# LCD_LED.net
KiCad netlist of a schematic drawn in Altium Designer
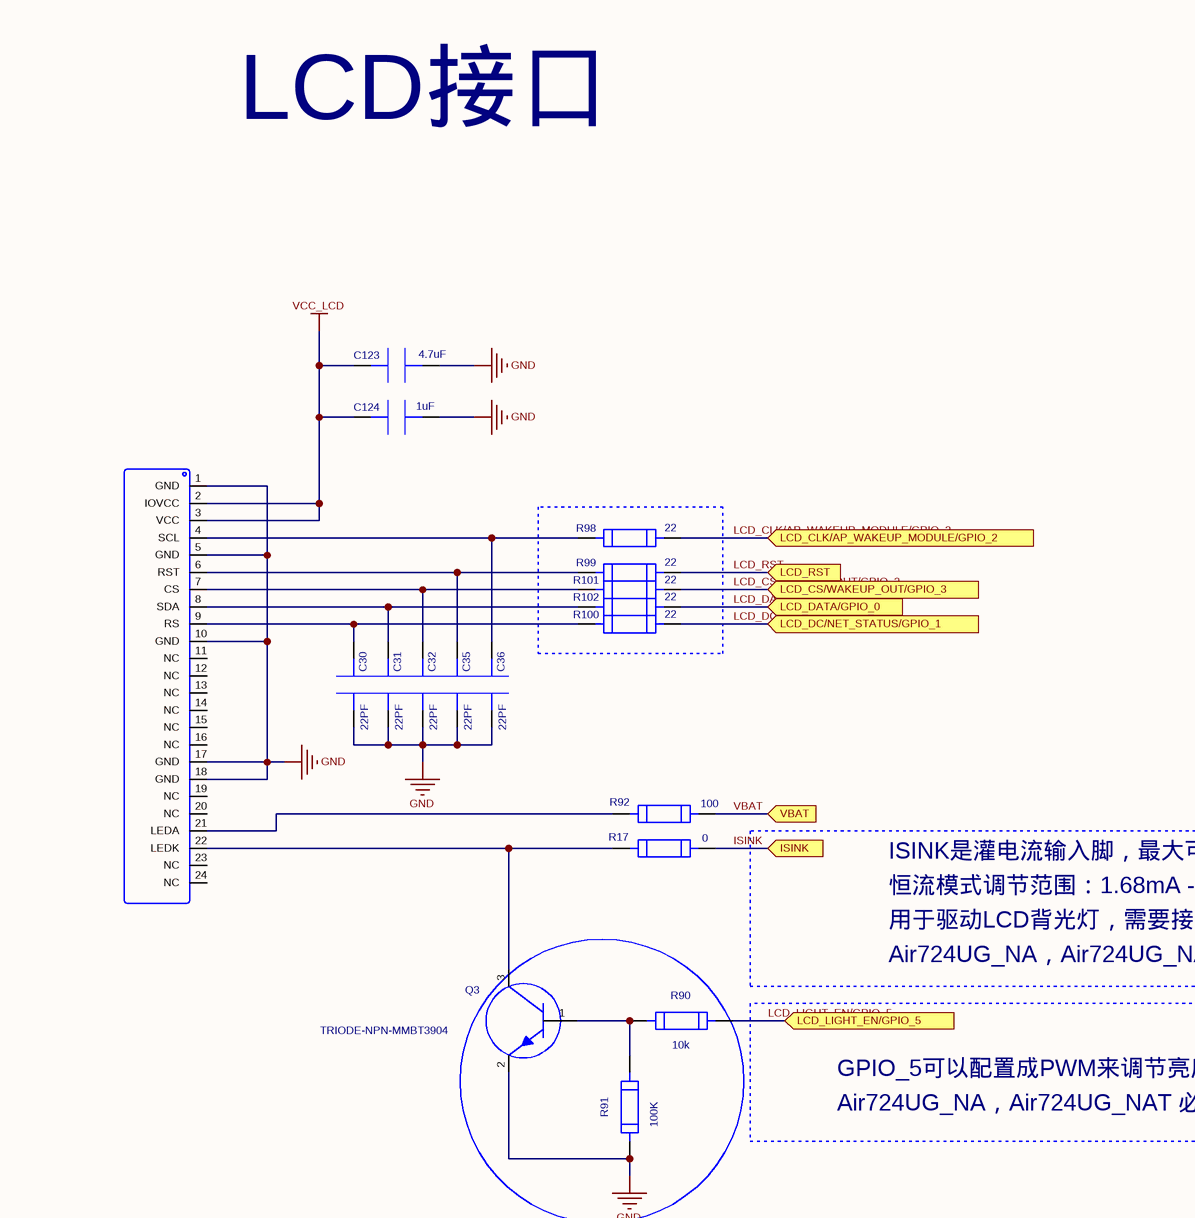
[diagram p0: LCD_LED.SchDoc, top left]
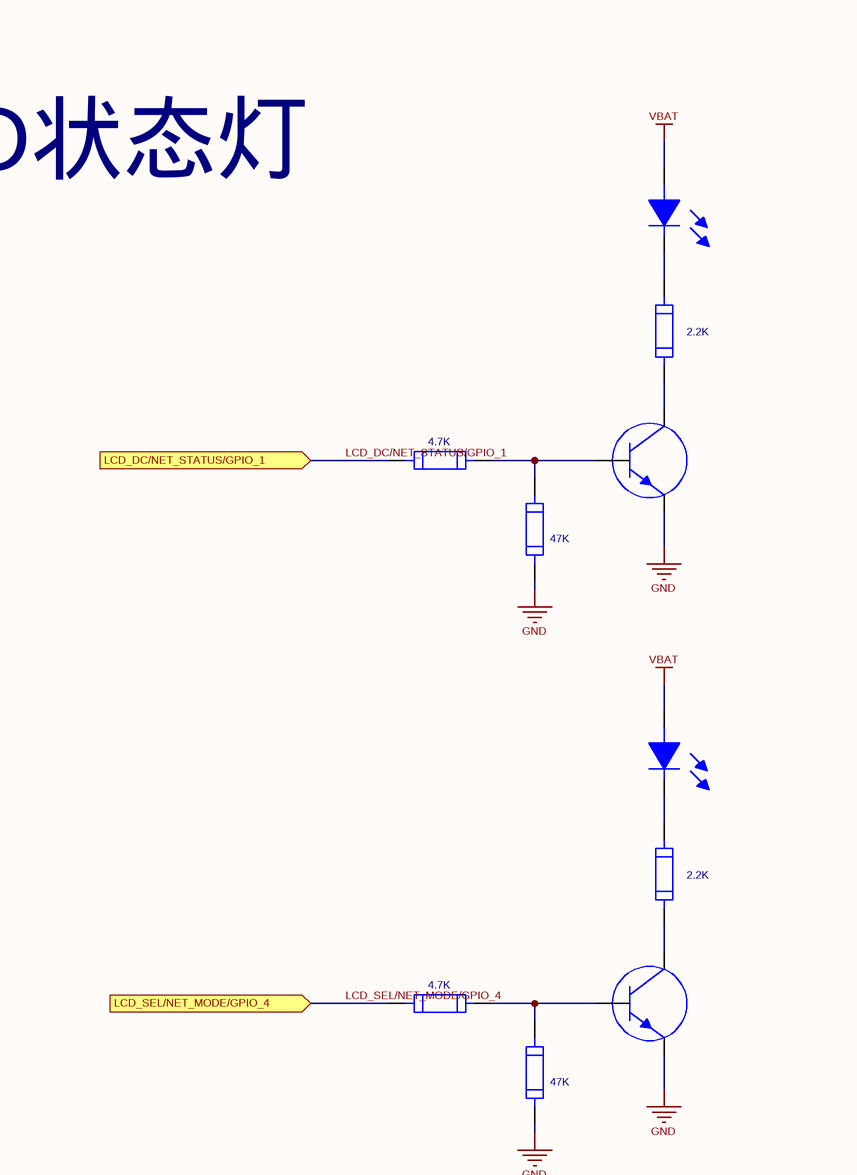
[diagram p1: LCD_LED.SchDoc, top right]
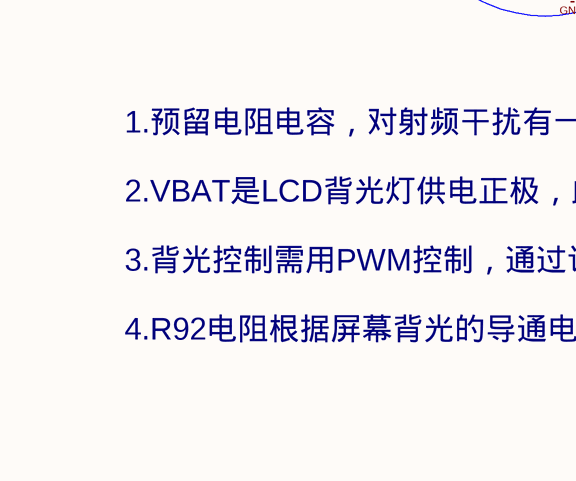
[diagram p2: LCD_LED.SchDoc, bottom left]
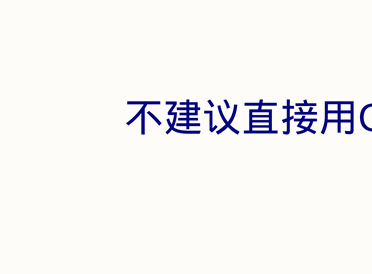
[diagram p3: LCD_LED.SchDoc, bottom middle]
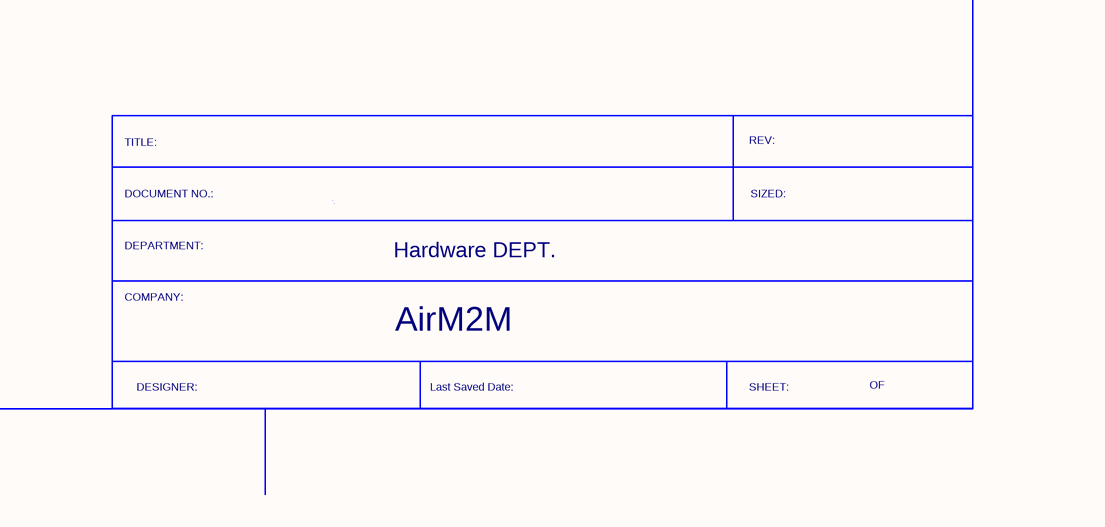
[diagram p4: LCD_LED.SchDoc, bottom right]

(export (version "E")
  (design (tool "Eeschema 10.0.6"))
  (components
    (comp (ref "C30")
      (value "22PF")
      (footprint "SC0402")
      (description "CAP CER C0G;22PF;+/-5%;50V;0402;0.5mm;ROHS")
      (fields (field (name "TOLERANCE") "+/-5%;") (field (name "Comment") "CAP-22PF-0402-C0G"))
      (libsource (lib "*") (part "CAP-22PF-0402-C0G"))
    )
    (comp (ref "C31")
      (value "22PF")
      (footprint "SC0402")
      (description "CAP CER C0G;22PF;+/-5%;50V;0402;0.5mm;ROHS")
      (fields (field (name "TOLERANCE") "+/-5%;") (field (name "Comment") "CAP-22PF-0402-C0G"))
      (libsource (lib "*") (part "CAP-22PF-0402-C0G"))
    )
    (comp (ref "C32")
      (value "22PF")
      (footprint "SC0402")
      (description "CAP CER C0G;22PF;+/-5%;50V;0402;0.5mm;ROHS")
      (fields (field (name "TOLERANCE") "+/-5%;") (field (name "Comment") "CAP-22PF-0402-C0G"))
      (libsource (lib "*") (part "CAP-22PF-0402-C0G"))
    )
    (comp (ref "C35")
      (value "22PF")
      (footprint "SC0402")
      (description "CAP CER C0G;22PF;+/-5%;50V;0402;0.5mm;ROHS")
      (fields (field (name "TOLERANCE") "+/-5%;") (field (name "Comment") "CAP-22PF-0402-C0G"))
      (libsource (lib "*") (part "CAP-22PF-0402-C0G"))
    )
    (comp (ref "C36")
      (value "22PF")
      (footprint "SC0402")
      (description "CAP CER C0G;22PF;+/-5%;50V;0402;0.5mm;ROHS")
      (fields (field (name "TOLERANCE") "+/-5%;") (field (name "Comment") "CAP-22PF-0402-C0G"))
      (libsource (lib "*") (part "CAP-22PF-0402-C0G"))
    )
    (comp (ref "C123")
      (value "4.7uF")
      (footprint "SC0603")
      (description "CAP CER X5R;4.7uF;+/-10%;6.3V;0603;0.8mm;ROHS")
      (fields (field (name "TOLERANCE") "+/-10%") (field (name "Comment") "CAP-4.7UF-0603-X5R"))
      (libsource (lib "*") (part "CAP-4.7UF-0603-X5R"))
    )
    (comp (ref "C124")
      (value "1uF")
      (footprint "SC0402")
      (description "CAP CER X5R;1uF;+/-10%;6.3V;0402;0.5mm;ROHS")
      (fields (field (name "TOLERANCE") "+/-10%") (field (name "Comment") "CAP-1UF-0402-X5R"))
      (libsource (lib "*") (part "CAP-1UF-0402-X5R"))
    )
    (comp (ref "D1")
      (value "DIODE-LED-RED-2.54")
      (footprint "DIP2X1-2.54")
      (description "LED red")
      (libsource (lib "*") (part "DIODE-LED-RED-2.54"))
    )
    (comp (ref "D3")
      (value "DIODE-LED-RED-2.54")
      (footprint "DIP2X1-2.54")
      (description "LED red")
      (libsource (lib "*") (part "DIODE-LED-RED-2.54"))
    )
    (comp (ref "P6")
      (value "FPC_0.5MM_24P_PULL_TYPE_H2.0MM_UNDER_THE")
      (footprint "FPC-SMD_AFC07-S24FCC-00")
      (fields
        (field (name "BOM_SUPPLIER_PART") "C11057")
        (field (name "BOM_MANUFACTURER_PART") "FPC 0.5MM 24P Pull type H2.0mm Under the next")
      )
      (libsource (lib "*") (part "FPC_0.5MM_24P_PULL_TYPE_H2.0MM_UNDER_THE"))
    )
    (comp (ref "Q3")
      (value "TRIODE-NPN-MMBT3904")
      (footprint "SOT-23(MMBT3904)")
      (description "Transistor;NPN;40V;200mA;SOT23;1.1mm;ROHS")
      (libsource (lib "") (part "TRIODE-NPN-MMBT3904_1"))
    )
    (comp (ref "Q5")
      (value "TRIODE-NPN-MMBT3904")
      (footprint "SOT-23(MMBT3904)")
      (description "Transistor;NPN;40V;200mA;SOT23;1.1mm;ROHS")
      (libsource (lib "*") (part "TRIODE-NPN-MMBT3904"))
    )
    (comp (ref "Q6")
      (value "TRIODE-NPN-MMBT3904")
      (footprint "SOT-23(MMBT3904)")
      (description "Transistor;NPN;40V;200mA;SOT23;1.1mm;ROHS")
      (libsource (lib "*") (part "TRIODE-NPN-MMBT3904"))
    )
    (comp (ref "R17")
      (value "0")
      (footprint "SR0402")
      (description "RES FILM;0;1A;0402;0.4mm;ROHS")
      (fields (field (name "Comment") "RES-0-0402"))
      (libsource (lib "*") (part "RES-0-0402"))
    )
    (comp (ref "R24")
      (value "4.7K")
      (footprint "SR0402")
      (description "RES FILM;4.7K;+/-5%;1/16W;0402;0.4mm;ROHS")
      (fields (field (name "TOLERANCE") "+/-5%") (field (name "Comment") "RES-4.7K-0402"))
      (libsource (lib "*") (part "RES-4.7K-0402"))
    )
    (comp (ref "R30")
      (value "47K")
      (footprint "SR0402")
      (description "RES FILM;4.7K;+/-5%;1/16W;0402;0.4mm;ROHS")
      (fields (field (name "TOLERANCE") "+/-5%") (field (name "Comment") "RES-4.7K-0402"))
      (libsource (lib "*") (part "RES-4.7K-0402"))
    )
    (comp (ref "R31")
      (value "2.2K")
      (footprint "SR0402")
      (description "RES FILM;4.7K;+/-5%;1/16W;0402;0.4mm;ROHS")
      (fields (field (name "TOLERANCE") "+/-5%") (field (name "Comment") "RES-4.7K-0402"))
      (libsource (lib "*") (part "RES-4.7K-0402"))
    )
    (comp (ref "R32")
      (value "4.7K")
      (footprint "SR0402")
      (description "RES FILM;4.7K;+/-5%;1/16W;0402;0.4mm;ROHS")
      (fields (field (name "TOLERANCE") "+/-5%") (field (name "Comment") "RES-4.7K-0402"))
      (libsource (lib "*") (part "RES-4.7K-0402"))
    )
    (comp (ref "R33")
      (value "47K")
      (footprint "SR0402")
      (description "RES FILM;4.7K;+/-5%;1/16W;0402;0.4mm;ROHS")
      (fields (field (name "TOLERANCE") "+/-5%") (field (name "Comment") "RES-4.7K-0402"))
      (libsource (lib "*") (part "RES-4.7K-0402"))
    )
    (comp (ref "R34")
      (value "2.2K")
      (footprint "SR0402")
      (description "RES FILM;4.7K;+/-5%;1/16W;0402;0.4mm;ROHS")
      (fields (field (name "TOLERANCE") "+/-5%") (field (name "Comment") "RES-4.7K-0402"))
      (libsource (lib "*") (part "RES-4.7K-0402"))
    )
    (comp (ref "R90")
      (value "10k")
      (footprint "SR0402")
      (description "RES FILM;10K;+/-5%;1/16W;0402;0.4mm;ROHS")
      (fields (field (name "TOLERANCE") "+/-5%") (field (name "Comment") "RES-10K-0402"))
      (libsource (lib "*") (part "RES-10K-0402"))
    )
    (comp (ref "R91")
      (value "100K")
      (footprint "SR0402")
      (description "RES FILM;100K;+/-5%;1/16W;0402;0.4mm;ROHS")
      (fields (field (name "TOLERANCE") "+/-5%") (field (name "Comment") "RES-100K-0402"))
      (libsource (lib "*") (part "RES-100K-0402"))
    )
    (comp (ref "R92")
      (value "100")
      (footprint "SR0603")
      (description "RES FILM;100;+/-5%;1/10W;0603;0.55mm;ROHS")
      (fields (field (name "TOLERANCE") "+/-5%") (field (name "Comment") "RES-100-0603"))
      (libsource (lib "*") (part "RES-100-0603"))
    )
    (comp (ref "R98")
      (value "22")
      (footprint "SR0402")
      (description "RES FILM;22;+/-5%;1/16W;0402;0.4mm;ROHS")
      (fields (field (name "TOLERANCE") "+/-5%") (field (name "Comment") "RES-22-0402"))
      (libsource (lib "*") (part "RES-22-0402"))
    )
    (comp (ref "R99")
      (value "22")
      (footprint "SR0402")
      (description "RES FILM;22;+/-5%;1/16W;0402;0.4mm;ROHS")
      (fields (field (name "TOLERANCE") "+/-5%") (field (name "Comment") "RES-22-0402"))
      (libsource (lib "*") (part "RES-22-0402"))
    )
    (comp (ref "R100")
      (value "22")
      (footprint "SR0402")
      (description "RES FILM;22;+/-5%;1/16W;0402;0.4mm;ROHS")
      (fields (field (name "TOLERANCE") "+/-5%") (field (name "Comment") "RES-22-0402"))
      (libsource (lib "*") (part "RES-22-0402"))
    )
    (comp (ref "R101")
      (value "22")
      (footprint "SR0402")
      (description "RES FILM;22;+/-5%;1/16W;0402;0.4mm;ROHS")
      (fields (field (name "TOLERANCE") "+/-5%") (field (name "Comment") "RES-22-0402"))
      (libsource (lib "*") (part "RES-22-0402"))
    )
    (comp (ref "R102")
      (value "22")
      (footprint "SR0402")
      (description "RES FILM;22;+/-5%;1/16W;0402;0.4mm;ROHS")
      (fields (field (name "TOLERANCE") "+/-5%") (field (name "Comment") "RES-22-0402"))
      (libsource (lib "*") (part "RES-22-0402"))
    )
  )
  (nets
    (net (code "1") (name "/ISINK") (class "Default")
      (node (ref "R17") (pin "2") (pinfunction "2_2") (pintype "passive"))
    )
    (net (code "2") (name "/LCD_CLK{slash}AP_WAKEUP_MODULE{slash}GPIO_2") (class "Default")
      (node (ref "R98") (pin "2") (pinfunction "2_2") (pintype "passive"))
    )
    (net (code "3") (name "/LCD_CS{slash}WAKEUP_OUT{slash}GPIO_3") (class "Default")
      (node (ref "R101") (pin "2") (pinfunction "2_2") (pintype "passive"))
    )
    (net (code "4") (name "/LCD_DATA{slash}GPIO_0") (class "Default")
      (node (ref "R102") (pin "2") (pinfunction "2_2") (pintype "passive"))
    )
    (net (code "5") (name "/LCD_DC{slash}NET_STATUS{slash}GPIO_1") (class "Default")
      (node (ref "R100") (pin "2") (pinfunction "2_2") (pintype "passive"))
      (node (ref "R32") (pin "1") (pinfunction "1_1") (pintype "passive"))
    )
    (net (code "6") (name "/LCD_LIGHT_EN{slash}GPIO_5") (class "Default")
      (node (ref "R90") (pin "2") (pinfunction "2_2") (pintype "passive"))
    )
    (net (code "7") (name "/LCD_RST") (class "Default")
      (node (ref "R99") (pin "2") (pinfunction "2_2") (pintype "passive"))
    )
    (net (code "8") (name "/LCD_SEL{slash}NET_MODE{slash}GPIO_4") (class "Default")
      (node (ref "R24") (pin "1") (pinfunction "1_1") (pintype "passive"))
    )
    (net (code "9") (name "GND") (class "Default")
      (node (ref "C123") (pin "1") (pinfunction "1_1") (pintype "passive"))
      (node (ref "C124") (pin "1") (pinfunction "1_1") (pintype "passive"))
      (node (ref "C30") (pin "2") (pinfunction "2_2") (pintype "passive"))
      (node (ref "C31") (pin "2") (pinfunction "2_2") (pintype "passive"))
      (node (ref "C32") (pin "2") (pinfunction "2_2") (pintype "passive"))
      (node (ref "C35") (pin "2") (pinfunction "2_2") (pintype "passive"))
      (node (ref "C36") (pin "2") (pinfunction "2_2") (pintype "passive"))
      (node (ref "P6") (pin "1") (pinfunction "GND_1") (pintype "passive"))
      (node (ref "P6") (pin "10") (pinfunction "GND_10") (pintype "passive"))
      (node (ref "P6") (pin "17") (pinfunction "GND_17") (pintype "passive"))
      (node (ref "P6") (pin "18") (pinfunction "GND_18") (pintype "passive"))
      (node (ref "P6") (pin "5") (pinfunction "GND_5") (pintype "passive"))
      (node (ref "Q3") (pin "2") (pinfunction "2_2") (pintype "passive"))
      (node (ref "Q5") (pin "2") (pinfunction "2_2") (pintype "passive"))
      (node (ref "Q6") (pin "2") (pinfunction "2_2") (pintype "passive"))
      (node (ref "R30") (pin "1") (pinfunction "1_1") (pintype "passive"))
      (node (ref "R33") (pin "1") (pinfunction "1_1") (pintype "passive"))
      (node (ref "R91") (pin "1") (pinfunction "1_1") (pintype "passive"))
    )
    (net (code "10") (name "Net-(D1-Pad2)") (class "Default")
      (node (ref "D1") (pin "2") (pinfunction "2_2") (pintype "passive"))
      (node (ref "R31") (pin "2") (pinfunction "2_2") (pintype "passive"))
    )
    (net (code "11") (name "Net-(D3-Pad2)") (class "Default")
      (node (ref "D3") (pin "2") (pinfunction "2_2") (pintype "passive"))
      (node (ref "R34") (pin "2") (pinfunction "2_2") (pintype "passive"))
    )
    (net (code "12") (name "Net-(P6-CS)") (class "Default")
      (node (ref "C32") (pin "1") (pinfunction "1_1") (pintype "passive"))
      (node (ref "P6") (pin "7") (pinfunction "CS_7") (pintype "passive"))
      (node (ref "R101") (pin "1") (pinfunction "1_1") (pintype "passive"))
    )
    (net (code "13") (name "Net-(P6-LEDA)") (class "Default")
      (node (ref "P6") (pin "21") (pinfunction "LEDA_21") (pintype "passive"))
      (node (ref "R92") (pin "2") (pinfunction "2_2") (pintype "passive"))
    )
    (net (code "14") (name "Net-(P6-LEDK)") (class "Default")
      (node (ref "P6") (pin "22") (pinfunction "LEDK_22") (pintype "passive"))
      (node (ref "Q3") (pin "3") (pinfunction "3_3") (pintype "passive"))
      (node (ref "R17") (pin "1") (pinfunction "1_1") (pintype "passive"))
    )
    (net (code "15") (name "Net-(P6-RS)") (class "Default")
      (node (ref "C30") (pin "1") (pinfunction "1_1") (pintype "passive"))
      (node (ref "P6") (pin "9") (pinfunction "RS_9") (pintype "passive"))
      (node (ref "R100") (pin "1") (pinfunction "1_1") (pintype "passive"))
    )
    (net (code "16") (name "Net-(P6-RST)") (class "Default")
      (node (ref "C35") (pin "1") (pinfunction "1_1") (pintype "passive"))
      (node (ref "P6") (pin "6") (pinfunction "RST_6") (pintype "passive"))
      (node (ref "R99") (pin "1") (pinfunction "1_1") (pintype "passive"))
    )
    (net (code "17") (name "Net-(P6-SCL)") (class "Default")
      (node (ref "C36") (pin "1") (pinfunction "1_1") (pintype "passive"))
      (node (ref "P6") (pin "4") (pinfunction "SCL_4") (pintype "passive"))
      (node (ref "R98") (pin "1") (pinfunction "1_1") (pintype "passive"))
    )
    (net (code "18") (name "Net-(P6-SDA)") (class "Default")
      (node (ref "C31") (pin "1") (pinfunction "1_1") (pintype "passive"))
      (node (ref "P6") (pin "8") (pinfunction "SDA_8") (pintype "passive"))
      (node (ref "R102") (pin "1") (pinfunction "1_1") (pintype "passive"))
    )
    (net (code "19") (name "Net-(Q3-Pad1)") (class "Default")
      (node (ref "Q3") (pin "1") (pinfunction "1_1") (pintype "passive"))
      (node (ref "R90") (pin "1") (pinfunction "1_1") (pintype "passive"))
      (node (ref "R91") (pin "2") (pinfunction "2_2") (pintype "passive"))
    )
    (net (code "20") (name "Net-(Q5-Pad1)") (class "Default")
      (node (ref "Q5") (pin "1") (pinfunction "1_1") (pintype "passive"))
      (node (ref "R32") (pin "2") (pinfunction "2_2") (pintype "passive"))
      (node (ref "R33") (pin "2") (pinfunction "2_2") (pintype "passive"))
    )
    (net (code "21") (name "Net-(Q5-Pad3)") (class "Default")
      (node (ref "Q5") (pin "3") (pinfunction "3_3") (pintype "passive"))
      (node (ref "R34") (pin "1") (pinfunction "1_1") (pintype "passive"))
    )
    (net (code "22") (name "Net-(Q6-Pad1)") (class "Default")
      (node (ref "Q6") (pin "1") (pinfunction "1_1") (pintype "passive"))
      (node (ref "R24") (pin "2") (pinfunction "2_2") (pintype "passive"))
      (node (ref "R30") (pin "2") (pinfunction "2_2") (pintype "passive"))
    )
    (net (code "23") (name "Net-(Q6-Pad3)") (class "Default")
      (node (ref "Q6") (pin "3") (pinfunction "3_3") (pintype "passive"))
      (node (ref "R31") (pin "1") (pinfunction "1_1") (pintype "passive"))
    )
    (net (code "24") (name "VBAT") (class "Default")
      (node (ref "D1") (pin "1") (pinfunction "1_1") (pintype "passive"))
      (node (ref "D3") (pin "1") (pinfunction "1_1") (pintype "passive"))
      (node (ref "R92") (pin "1") (pinfunction "1_1") (pintype "passive"))
    )
    (net (code "25") (name "VCC_LCD") (class "Default")
      (node (ref "C123") (pin "2") (pinfunction "2_2") (pintype "passive"))
      (node (ref "C124") (pin "2") (pinfunction "2_2") (pintype "passive"))
      (node (ref "P6") (pin "2") (pinfunction "IOVCC_2") (pintype "passive"))
      (node (ref "P6") (pin "3") (pinfunction "VCC_3") (pintype "passive"))
    )
    (net (code "26") (name "unconnected-(P6-NC-Pad11)") (class "Default")
      (node (ref "P6") (pin "11") (pinfunction "NC_11") (pintype "passive"))
    )
    (net (code "27") (name "unconnected-(P6-NC-Pad12)") (class "Default")
      (node (ref "P6") (pin "12") (pinfunction "NC_12") (pintype "passive"))
    )
    (net (code "28") (name "unconnected-(P6-NC-Pad13)") (class "Default")
      (node (ref "P6") (pin "13") (pinfunction "NC_13") (pintype "passive"))
    )
    (net (code "29") (name "unconnected-(P6-NC-Pad14)") (class "Default")
      (node (ref "P6") (pin "14") (pinfunction "NC_14") (pintype "passive"))
    )
    (net (code "30") (name "unconnected-(P6-NC-Pad15)") (class "Default")
      (node (ref "P6") (pin "15") (pinfunction "NC_15") (pintype "passive"))
    )
    (net (code "31") (name "unconnected-(P6-NC-Pad16)") (class "Default")
      (node (ref "P6") (pin "16") (pinfunction "NC_16") (pintype "passive"))
    )
    (net (code "32") (name "unconnected-(P6-NC-Pad19)") (class "Default")
      (node (ref "P6") (pin "19") (pinfunction "NC_19") (pintype "passive"))
    )
    (net (code "33") (name "unconnected-(P6-NC-Pad20)") (class "Default")
      (node (ref "P6") (pin "20") (pinfunction "NC_20") (pintype "passive"))
    )
    (net (code "34") (name "unconnected-(P6-NC-Pad23)") (class "Default")
      (node (ref "P6") (pin "23") (pinfunction "NC_23") (pintype "passive"))
    )
    (net (code "35") (name "unconnected-(P6-NC-Pad24)") (class "Default")
      (node (ref "P6") (pin "24") (pinfunction "NC_24") (pintype "passive"))
    )
  )
)
